# led_cube_final.net
KiCad netlist of a schematic drawn in EAGLE
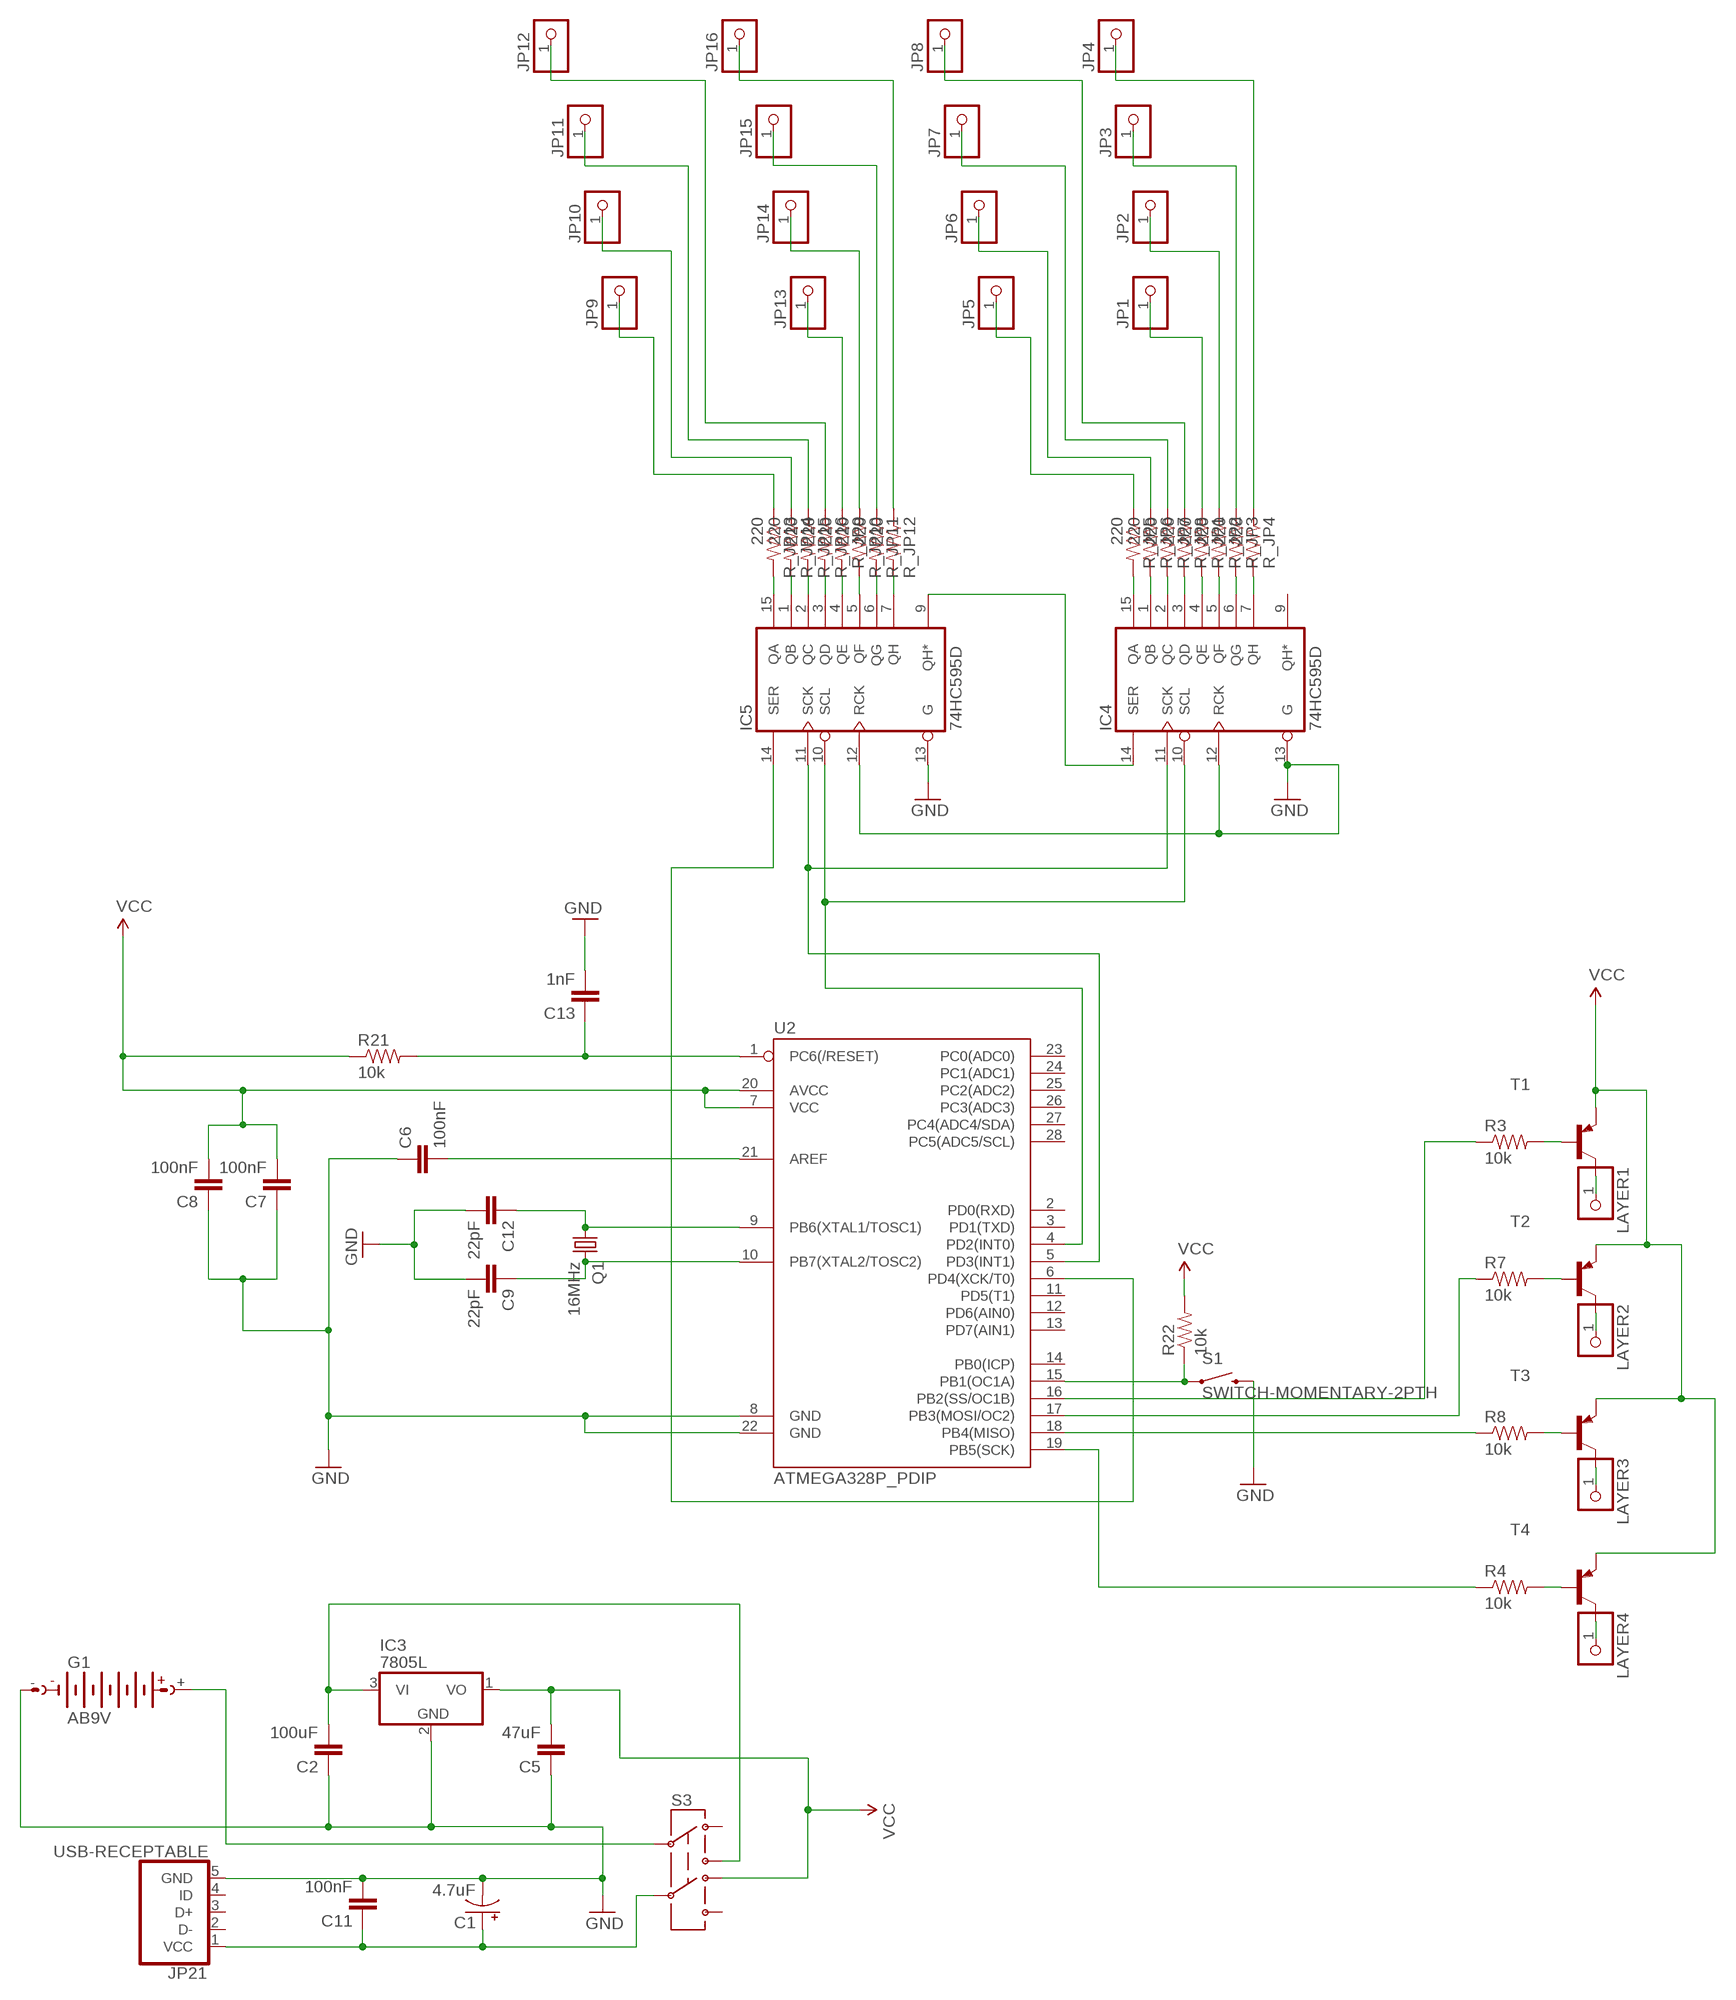
[diagram p0: schematic, sheet 1]

(export (version "E")
  (design (tool "Eeschema 10.0.6"))
  (components
    (comp (ref "C1")
      (value "4.7uF")
      (footprint "eagle-import:E2-5")
      (libsource (lib "eagle-import") (part "CPOL-USE2-5"))
    )
    (comp (ref "C2")
      (value "100uF")
      (footprint "eagle-import:0805")
      (libsource (lib "eagle-import") (part "CAP0805"))
    )
    (comp (ref "C5")
      (value "47uF")
      (footprint "eagle-import:0805")
      (libsource (lib "eagle-import") (part "CAP0805"))
    )
    (comp (ref "C6")
      (value "100nF")
      (footprint "eagle-import:0805")
      (libsource (lib "eagle-import") (part "CAP0805"))
    )
    (comp (ref "C7")
      (value "100nF")
      (footprint "eagle-import:0805")
      (libsource (lib "eagle-import") (part "CAP0805"))
    )
    (comp (ref "C8")
      (value "100nF")
      (footprint "eagle-import:0805")
      (libsource (lib "eagle-import") (part "CAP0805"))
    )
    (comp (ref "C9")
      (value "22pF")
      (footprint "eagle-import:0805")
      (libsource (lib "eagle-import") (part "CAP0805"))
    )
    (comp (ref "C11")
      (value "100nF")
      (footprint "eagle-import:0805")
      (libsource (lib "eagle-import") (part "CAP0805"))
    )
    (comp (ref "C12")
      (value "22pF")
      (footprint "eagle-import:0805")
      (libsource (lib "eagle-import") (part "CAP0805"))
    )
    (comp (ref "C13")
      (value "1nF")
      (footprint "eagle-import:0805")
      (libsource (lib "eagle-import") (part "CAP0805"))
    )
    (comp (ref "G1")
      (value "AB9V")
      (footprint "eagle-import:AB9V")
      (libsource (lib "eagle-import") (part "AB9V"))
    )
    (comp (ref "IC3")
      (value "7805L")
      (footprint "eagle-import:TO92")
      (libsource (lib "eagle-import") (part "78L05"))
    )
    (comp (ref "IC4")
      (value "74HC595D")
      (footprint "eagle-import:SO16")
      (libsource (lib "eagle-import") (part "74595DHC"))
    )
    (comp (ref "IC5")
      (value "74HC595D")
      (footprint "eagle-import:SO16")
      (libsource (lib "eagle-import") (part "74595DHC"))
    )
    (comp (ref "JP1")
      (value "PINHD-1X1")
      (footprint "eagle-import:1X01")
      (libsource (lib "eagle-import") (part "PINHD-1X1"))
    )
    (comp (ref "JP2")
      (value "PINHD-1X1")
      (footprint "eagle-import:1X01")
      (libsource (lib "eagle-import") (part "PINHD-1X1"))
    )
    (comp (ref "JP3")
      (value "PINHD-1X1")
      (footprint "eagle-import:1X01")
      (libsource (lib "eagle-import") (part "PINHD-1X1"))
    )
    (comp (ref "JP4")
      (value "PINHD-1X1")
      (footprint "eagle-import:1X01")
      (libsource (lib "eagle-import") (part "PINHD-1X1"))
    )
    (comp (ref "JP5")
      (value "PINHD-1X1")
      (footprint "eagle-import:1X01")
      (libsource (lib "eagle-import") (part "PINHD-1X1"))
    )
    (comp (ref "JP6")
      (value "PINHD-1X1")
      (footprint "eagle-import:1X01")
      (libsource (lib "eagle-import") (part "PINHD-1X1"))
    )
    (comp (ref "JP7")
      (value "PINHD-1X1")
      (footprint "eagle-import:1X01")
      (libsource (lib "eagle-import") (part "PINHD-1X1"))
    )
    (comp (ref "JP8")
      (value "PINHD-1X1")
      (footprint "eagle-import:1X01")
      (libsource (lib "eagle-import") (part "PINHD-1X1"))
    )
    (comp (ref "JP9")
      (value "PINHD-1X1")
      (footprint "eagle-import:1X01")
      (libsource (lib "eagle-import") (part "PINHD-1X1"))
    )
    (comp (ref "JP10")
      (value "PINHD-1X1")
      (footprint "eagle-import:1X01")
      (libsource (lib "eagle-import") (part "PINHD-1X1"))
    )
    (comp (ref "JP11")
      (value "PINHD-1X1")
      (footprint "eagle-import:1X01")
      (libsource (lib "eagle-import") (part "PINHD-1X1"))
    )
    (comp (ref "JP12")
      (value "PINHD-1X1")
      (footprint "eagle-import:1X01")
      (libsource (lib "eagle-import") (part "PINHD-1X1"))
    )
    (comp (ref "JP13")
      (value "PINHD-1X1")
      (footprint "eagle-import:1X01")
      (libsource (lib "eagle-import") (part "PINHD-1X1"))
    )
    (comp (ref "JP14")
      (value "PINHD-1X1")
      (footprint "eagle-import:1X01")
      (libsource (lib "eagle-import") (part "PINHD-1X1"))
    )
    (comp (ref "JP15")
      (value "PINHD-1X1")
      (footprint "eagle-import:1X01")
      (libsource (lib "eagle-import") (part "PINHD-1X1"))
    )
    (comp (ref "JP16")
      (value "PINHD-1X1")
      (footprint "eagle-import:1X01")
      (libsource (lib "eagle-import") (part "PINHD-1X1"))
    )
    (comp (ref "JP21")
      (value "USB-RECEPTABLE")
      (footprint "eagle-import:FCI-10103594-0001LF")
      (libsource (lib "eagle-import") (part "USB-RECEPTABLE"))
    )
    (comp (ref "LAYER1")
      (value "PINHD-1X1")
      (footprint "eagle-import:1X01")
      (libsource (lib "eagle-import") (part "PINHD-1X1"))
    )
    (comp (ref "LAYER2")
      (value "PINHD-1X1")
      (footprint "eagle-import:1X01")
      (libsource (lib "eagle-import") (part "PINHD-1X1"))
    )
    (comp (ref "LAYER3")
      (value "PINHD-1X1")
      (footprint "eagle-import:1X01")
      (libsource (lib "eagle-import") (part "PINHD-1X1"))
    )
    (comp (ref "LAYER4")
      (value "PINHD-1X1")
      (footprint "eagle-import:1X01")
      (libsource (lib "eagle-import") (part "PINHD-1X1"))
    )
    (comp (ref "Q1")
      (value "16MHz")
      (footprint "eagle-import:HC49_S")
      (libsource (lib "eagle-import") (part "CRYSTALHC49S"))
    )
    (comp (ref "R3")
      (value "10k")
      (footprint "eagle-import:0805")
      (libsource (lib "eagle-import") (part "RESISTOR0805-RES"))
    )
    (comp (ref "R4")
      (value "10k")
      (footprint "eagle-import:0805")
      (libsource (lib "eagle-import") (part "RESISTOR0805-RES"))
    )
    (comp (ref "R7")
      (value "10k")
      (footprint "eagle-import:0805")
      (libsource (lib "eagle-import") (part "RESISTOR0805-RES"))
    )
    (comp (ref "R8")
      (value "10k")
      (footprint "eagle-import:0805")
      (libsource (lib "eagle-import") (part "RESISTOR0805-RES"))
    )
    (comp (ref "R21")
      (value "10k")
      (footprint "eagle-import:0805")
      (libsource (lib "eagle-import") (part "RESISTOR0805-RES"))
    )
    (comp (ref "R22")
      (value "10k")
      (footprint "eagle-import:0805")
      (libsource (lib "eagle-import") (part "RESISTOR0805-RES"))
    )
    (comp (ref "R_JP1")
      (value "220")
      (footprint "eagle-import:0805")
      (libsource (lib "eagle-import") (part "RESISTOR0805-RES"))
    )
    (comp (ref "R_JP2")
      (value "220")
      (footprint "eagle-import:0805")
      (libsource (lib "eagle-import") (part "RESISTOR0805-RES"))
    )
    (comp (ref "R_JP3")
      (value "220")
      (footprint "eagle-import:0805")
      (libsource (lib "eagle-import") (part "RESISTOR0805-RES"))
    )
    (comp (ref "R_JP4")
      (value "220")
      (footprint "eagle-import:0805")
      (libsource (lib "eagle-import") (part "RESISTOR0805-RES"))
    )
    (comp (ref "R_JP5")
      (value "220")
      (footprint "eagle-import:0805")
      (libsource (lib "eagle-import") (part "RESISTOR0805-RES"))
    )
    (comp (ref "R_JP6")
      (value "220")
      (footprint "eagle-import:0805")
      (libsource (lib "eagle-import") (part "RESISTOR0805-RES"))
    )
    (comp (ref "R_JP7")
      (value "220")
      (footprint "eagle-import:0805")
      (libsource (lib "eagle-import") (part "RESISTOR0805-RES"))
    )
    (comp (ref "R_JP8")
      (value "220")
      (footprint "eagle-import:0805")
      (libsource (lib "eagle-import") (part "RESISTOR0805-RES"))
    )
    (comp (ref "R_JP9")
      (value "220")
      (footprint "eagle-import:0805")
      (libsource (lib "eagle-import") (part "RESISTOR0805-RES"))
    )
    (comp (ref "R_JP10")
      (value "220")
      (footprint "eagle-import:0805")
      (libsource (lib "eagle-import") (part "RESISTOR0805-RES"))
    )
    (comp (ref "R_JP11")
      (value "220")
      (footprint "eagle-import:0805")
      (libsource (lib "eagle-import") (part "RESISTOR0805-RES"))
    )
    (comp (ref "R_JP12")
      (value "220")
      (footprint "eagle-import:0805")
      (libsource (lib "eagle-import") (part "RESISTOR0805-RES"))
    )
    (comp (ref "R_JP13")
      (value "220")
      (footprint "eagle-import:0805")
      (libsource (lib "eagle-import") (part "RESISTOR0805-RES"))
    )
    (comp (ref "R_JP14")
      (value "220")
      (footprint "eagle-import:0805")
      (libsource (lib "eagle-import") (part "RESISTOR0805-RES"))
    )
    (comp (ref "R_JP15")
      (value "220")
      (footprint "eagle-import:0805")
      (libsource (lib "eagle-import") (part "RESISTOR0805-RES"))
    )
    (comp (ref "R_JP16")
      (value "220")
      (footprint "eagle-import:0805")
      (libsource (lib "eagle-import") (part "RESISTOR0805-RES"))
    )
    (comp (ref "S1")
      (value "SWITCH-MOMENTARY-2PTH")
      (footprint "eagle-import:TACTILE-PTH")
      (libsource (lib "eagle-import") (part "SWITCH-MOMENTARY-2PTH"))
    )
    (comp (ref "S3")
      (value "SWITCH-DPDTOS")
      (footprint "eagle-import:OS")
      (libsource (lib "eagle-import") (part "SWITCH-DPDTOS"))
    )
    (comp (ref "T1")
      (value "BC327-16-PNP-TO92-EBC")
      (footprint "eagle-import:TO92-EBC")
      (libsource (lib "eagle-import") (part "-PNP-TO92-EBCBC327-16"))
    )
    (comp (ref "T2")
      (value "BC327-16-PNP-TO92-EBC")
      (footprint "eagle-import:TO92-EBC")
      (libsource (lib "eagle-import") (part "-PNP-TO92-EBCBC327-16"))
    )
    (comp (ref "T3")
      (value "BC327-16-PNP-TO92-EBC")
      (footprint "eagle-import:TO92-EBC")
      (libsource (lib "eagle-import") (part "-PNP-TO92-EBCBC327-16"))
    )
    (comp (ref "T4")
      (value "BC327-16-PNP-TO92-EBC")
      (footprint "eagle-import:TO92-EBC")
      (libsource (lib "eagle-import") (part "-PNP-TO92-EBCBC327-16"))
    )
    (comp (ref "U2")
      (value "ATMEGA328P_PDIP")
      (footprint "eagle-import:DIL28-3")
      (libsource (lib "eagle-import") (part "ATMEGA328P_PDIP"))
    )
  )
  (nets
    (net (code "1") (name "GND") (class "Default")
      (node (ref "C1") (pin "-") (pinfunction "-_-") (pintype "passive"))
      (node (ref "C11") (pin "2") (pinfunction "2_2") (pintype "passive"))
      (node (ref "C12") (pin "2") (pinfunction "2_2") (pintype "passive"))
      (node (ref "C13") (pin "2") (pinfunction "2_2") (pintype "passive"))
      (node (ref "C2") (pin "1") (pinfunction "1_1") (pintype "passive"))
      (node (ref "C5") (pin "1") (pinfunction "1_1") (pintype "passive"))
      (node (ref "C6") (pin "1") (pinfunction "1_1") (pintype "passive"))
      (node (ref "C7") (pin "1") (pinfunction "1_1") (pintype "passive"))
      (node (ref "C8") (pin "1") (pinfunction "1_1") (pintype "passive"))
      (node (ref "C9") (pin "2") (pinfunction "2_2") (pintype "passive"))
      (node (ref "G1") (pin "-") (pinfunction "-_-") (pintype "passive"))
      (node (ref "IC3") (pin "2") (pinfunction "GND_2") (pintype "passive"))
      (node (ref "IC4") (pin "12") (pinfunction "RCK_12") (pintype "input"))
      (node (ref "IC4") (pin "13") (pinfunction "G_13") (pintype "input"))
      (node (ref "IC5") (pin "12") (pinfunction "RCK_12") (pintype "input"))
      (node (ref "IC5") (pin "13") (pinfunction "G_13") (pintype "input"))
      (node (ref "JP21") (pin "5") (pinfunction "GND_5") (pintype "bidirectional"))
      (node (ref "S1") (pin "3") (pinfunction "2_3") (pintype "passive"))
      (node (ref "U2") (pin "22") (pinfunction "GND_22") (pintype "bidirectional"))
      (node (ref "U2") (pin "8") (pinfunction "GND_8") (pintype "bidirectional"))
    )
    (net (code "2") (name "Net-(G1-Pad+)") (class "Default")
      (node (ref "G1") (pin "+") (pinfunction "+_+") (pintype "passive"))
      (node (ref "S3") (pin "2") (pinfunction "2_2") (pintype "bidirectional"))
    )
    (net (code "3") (name "Net-(IC3-VI)") (class "Default")
      (node (ref "C2") (pin "2") (pinfunction "2_2") (pintype "passive"))
      (node (ref "IC3") (pin "3") (pinfunction "VI_3") (pintype "input"))
      (node (ref "S3") (pin "3") (pinfunction "3_3") (pintype "bidirectional"))
    )
    (net (code "4") (name "Net-(IC4A-QA)") (class "Default")
      (node (ref "IC4") (pin "15") (pinfunction "QA_15") (pintype "tri_state"))
      (node (ref "R_JP5") (pin "2") (pinfunction "2_2") (pintype "passive"))
    )
    (net (code "5") (name "Net-(IC4A-QB)") (class "Default")
      (node (ref "IC4") (pin "1") (pinfunction "QB_1") (pintype "tri_state"))
      (node (ref "R_JP6") (pin "2") (pinfunction "2_2") (pintype "passive"))
    )
    (net (code "6") (name "Net-(IC4A-QC)") (class "Default")
      (node (ref "IC4") (pin "2") (pinfunction "QC_2") (pintype "tri_state"))
      (node (ref "R_JP7") (pin "2") (pinfunction "2_2") (pintype "passive"))
    )
    (net (code "7") (name "Net-(IC4A-QD)") (class "Default")
      (node (ref "IC4") (pin "3") (pinfunction "QD_3") (pintype "tri_state"))
      (node (ref "R_JP8") (pin "2") (pinfunction "2_2") (pintype "passive"))
    )
    (net (code "8") (name "Net-(IC4A-QE)") (class "Default")
      (node (ref "IC4") (pin "4") (pinfunction "QE_4") (pintype "tri_state"))
      (node (ref "R_JP1") (pin "2") (pinfunction "2_2") (pintype "passive"))
    )
    (net (code "9") (name "Net-(IC4A-QF)") (class "Default")
      (node (ref "IC4") (pin "5") (pinfunction "QF_5") (pintype "tri_state"))
      (node (ref "R_JP2") (pin "2") (pinfunction "2_2") (pintype "passive"))
    )
    (net (code "10") (name "Net-(IC4A-QG)") (class "Default")
      (node (ref "IC4") (pin "6") (pinfunction "QG_6") (pintype "tri_state"))
      (node (ref "R_JP3") (pin "2") (pinfunction "2_2") (pintype "passive"))
    )
    (net (code "11") (name "Net-(IC4A-QH)") (class "Default")
      (node (ref "IC4") (pin "7") (pinfunction "QH_7") (pintype "tri_state"))
      (node (ref "R_JP4") (pin "2") (pinfunction "2_2") (pintype "passive"))
    )
    (net (code "12") (name "Net-(IC4A-SCK)") (class "Default")
      (node (ref "IC4") (pin "11") (pinfunction "SCK_11") (pintype "input"))
      (node (ref "IC5") (pin "11") (pinfunction "SCK_11") (pintype "input"))
      (node (ref "U2") (pin "5") (pinfunction "PD3(INT1)_5") (pintype "bidirectional"))
    )
    (net (code "13") (name "Net-(IC4A-SCL)") (class "Default")
      (node (ref "IC4") (pin "10") (pinfunction "SCL_10") (pintype "input"))
      (node (ref "IC5") (pin "10") (pinfunction "SCL_10") (pintype "input"))
      (node (ref "U2") (pin "4") (pinfunction "PD2(INT0)_4") (pintype "bidirectional"))
    )
    (net (code "14") (name "Net-(IC4A-SER)") (class "Default")
      (node (ref "IC4") (pin "14") (pinfunction "SER_14") (pintype "input"))
      (node (ref "IC5") (pin "9") (pinfunction "QH*_9") (pintype "tri_state"))
    )
    (net (code "15") (name "Net-(IC5A-QA)") (class "Default")
      (node (ref "IC5") (pin "15") (pinfunction "QA_15") (pintype "tri_state"))
      (node (ref "R_JP13") (pin "2") (pinfunction "2_2") (pintype "passive"))
    )
    (net (code "16") (name "Net-(IC5A-QB)") (class "Default")
      (node (ref "IC5") (pin "1") (pinfunction "QB_1") (pintype "tri_state"))
      (node (ref "R_JP14") (pin "2") (pinfunction "2_2") (pintype "passive"))
    )
    (net (code "17") (name "Net-(IC5A-QC)") (class "Default")
      (node (ref "IC5") (pin "2") (pinfunction "QC_2") (pintype "tri_state"))
      (node (ref "R_JP15") (pin "2") (pinfunction "2_2") (pintype "passive"))
    )
    (net (code "18") (name "Net-(IC5A-QD)") (class "Default")
      (node (ref "IC5") (pin "3") (pinfunction "QD_3") (pintype "tri_state"))
      (node (ref "R_JP16") (pin "2") (pinfunction "2_2") (pintype "passive"))
    )
    (net (code "19") (name "Net-(IC5A-QE)") (class "Default")
      (node (ref "IC5") (pin "4") (pinfunction "QE_4") (pintype "tri_state"))
      (node (ref "R_JP9") (pin "2") (pinfunction "2_2") (pintype "passive"))
    )
    (net (code "20") (name "Net-(IC5A-QF)") (class "Default")
      (node (ref "IC5") (pin "5") (pinfunction "QF_5") (pintype "tri_state"))
      (node (ref "R_JP10") (pin "2") (pinfunction "2_2") (pintype "passive"))
    )
    (net (code "21") (name "Net-(IC5A-QG)") (class "Default")
      (node (ref "IC5") (pin "6") (pinfunction "QG_6") (pintype "tri_state"))
      (node (ref "R_JP11") (pin "2") (pinfunction "2_2") (pintype "passive"))
    )
    (net (code "22") (name "Net-(IC5A-QH)") (class "Default")
      (node (ref "IC5") (pin "7") (pinfunction "QH_7") (pintype "tri_state"))
      (node (ref "R_JP12") (pin "2") (pinfunction "2_2") (pintype "passive"))
    )
    (net (code "23") (name "Net-(IC5A-SER)") (class "Default")
      (node (ref "IC5") (pin "14") (pinfunction "SER_14") (pintype "input"))
      (node (ref "U2") (pin "6") (pinfunction "PD4(XCK/T0)_6") (pintype "bidirectional"))
    )
    (net (code "24") (name "Net-(JP1-Pad1)") (class "Default")
      (node (ref "JP1") (pin "1") (pinfunction "1_1") (pintype "passive"))
      (node (ref "R_JP1") (pin "1") (pinfunction "1_1") (pintype "passive"))
    )
    (net (code "25") (name "Net-(JP2-Pad1)") (class "Default")
      (node (ref "JP2") (pin "1") (pinfunction "1_1") (pintype "passive"))
      (node (ref "R_JP2") (pin "1") (pinfunction "1_1") (pintype "passive"))
    )
    (net (code "26") (name "Net-(JP3-Pad1)") (class "Default")
      (node (ref "JP3") (pin "1") (pinfunction "1_1") (pintype "passive"))
      (node (ref "R_JP3") (pin "1") (pinfunction "1_1") (pintype "passive"))
    )
    (net (code "27") (name "Net-(JP4-Pad1)") (class "Default")
      (node (ref "JP4") (pin "1") (pinfunction "1_1") (pintype "passive"))
      (node (ref "R_JP4") (pin "1") (pinfunction "1_1") (pintype "passive"))
    )
    (net (code "28") (name "Net-(JP5-Pad1)") (class "Default")
      (node (ref "JP5") (pin "1") (pinfunction "1_1") (pintype "passive"))
      (node (ref "R_JP5") (pin "1") (pinfunction "1_1") (pintype "passive"))
    )
    (net (code "29") (name "Net-(JP6-Pad1)") (class "Default")
      (node (ref "JP6") (pin "1") (pinfunction "1_1") (pintype "passive"))
      (node (ref "R_JP6") (pin "1") (pinfunction "1_1") (pintype "passive"))
    )
    (net (code "30") (name "Net-(JP7-Pad1)") (class "Default")
      (node (ref "JP7") (pin "1") (pinfunction "1_1") (pintype "passive"))
      (node (ref "R_JP7") (pin "1") (pinfunction "1_1") (pintype "passive"))
    )
    (net (code "31") (name "Net-(JP8-Pad1)") (class "Default")
      (node (ref "JP8") (pin "1") (pinfunction "1_1") (pintype "passive"))
      (node (ref "R_JP8") (pin "1") (pinfunction "1_1") (pintype "passive"))
    )
    (net (code "32") (name "Net-(JP9-Pad1)") (class "Default")
      (node (ref "JP9") (pin "1") (pinfunction "1_1") (pintype "passive"))
      (node (ref "R_JP13") (pin "1") (pinfunction "1_1") (pintype "passive"))
    )
    (net (code "33") (name "Net-(JP10-Pad1)") (class "Default")
      (node (ref "JP10") (pin "1") (pinfunction "1_1") (pintype "passive"))
      (node (ref "R_JP14") (pin "1") (pinfunction "1_1") (pintype "passive"))
    )
    (net (code "34") (name "Net-(JP11-Pad1)") (class "Default")
      (node (ref "JP11") (pin "1") (pinfunction "1_1") (pintype "passive"))
      (node (ref "R_JP15") (pin "1") (pinfunction "1_1") (pintype "passive"))
    )
    (net (code "35") (name "Net-(JP12-Pad1)") (class "Default")
      (node (ref "JP12") (pin "1") (pinfunction "1_1") (pintype "passive"))
      (node (ref "R_JP16") (pin "1") (pinfunction "1_1") (pintype "passive"))
    )
    (net (code "36") (name "Net-(JP13-Pad1)") (class "Default")
      (node (ref "JP13") (pin "1") (pinfunction "1_1") (pintype "passive"))
      (node (ref "R_JP9") (pin "1") (pinfunction "1_1") (pintype "passive"))
    )
    (net (code "37") (name "Net-(JP14-Pad1)") (class "Default")
      (node (ref "JP14") (pin "1") (pinfunction "1_1") (pintype "passive"))
      (node (ref "R_JP10") (pin "1") (pinfunction "1_1") (pintype "passive"))
    )
    (net (code "38") (name "Net-(JP15-Pad1)") (class "Default")
      (node (ref "JP15") (pin "1") (pinfunction "1_1") (pintype "passive"))
      (node (ref "R_JP11") (pin "1") (pinfunction "1_1") (pintype "passive"))
    )
    (net (code "39") (name "Net-(JP16-Pad1)") (class "Default")
      (node (ref "JP16") (pin "1") (pinfunction "1_1") (pintype "passive"))
      (node (ref "R_JP12") (pin "1") (pinfunction "1_1") (pintype "passive"))
    )
    (net (code "40") (name "Net-(JP21-VCC)") (class "Default")
      (node (ref "C1") (pin "+") (pinfunction "+_+") (pintype "passive"))
      (node (ref "C11") (pin "1") (pinfunction "1_1") (pintype "passive"))
      (node (ref "JP21") (pin "1") (pinfunction "VCC_1") (pintype "bidirectional"))
      (node (ref "S3") (pin "5") (pinfunction "5_5") (pintype "bidirectional"))
    )
    (net (code "41") (name "Net-(LAYER1-Pad1)") (class "Default")
      (node (ref "LAYER1") (pin "1") (pinfunction "1_1") (pintype "passive"))
      (node (ref "T1") (pin "C") (pinfunction "C_C") (pintype "passive"))
    )
    (net (code "42") (name "Net-(LAYER2-Pad1)") (class "Default")
      (node (ref "LAYER2") (pin "1") (pinfunction "1_1") (pintype "passive"))
      (node (ref "T2") (pin "C") (pinfunction "C_C") (pintype "passive"))
    )
    (net (code "43") (name "Net-(LAYER3-Pad1)") (class "Default")
      (node (ref "LAYER3") (pin "1") (pinfunction "1_1") (pintype "passive"))
      (node (ref "T3") (pin "C") (pinfunction "C_C") (pintype "passive"))
    )
    (net (code "44") (name "Net-(LAYER4-Pad1)") (class "Default")
      (node (ref "LAYER4") (pin "1") (pinfunction "1_1") (pintype "passive"))
      (node (ref "T4") (pin "C") (pinfunction "C_C") (pintype "passive"))
    )
    (net (code "45") (name "Net-(R3-Pad2)") (class "Default")
      (node (ref "R3") (pin "2") (pinfunction "2_2") (pintype "passive"))
      (node (ref "T1") (pin "B") (pinfunction "B_B") (pintype "passive"))
    )
    (net (code "46") (name "Net-(R4-Pad2)") (class "Default")
      (node (ref "R4") (pin "2") (pinfunction "2_2") (pintype "passive"))
      (node (ref "T4") (pin "B") (pinfunction "B_B") (pintype "passive"))
    )
    (net (code "47") (name "Net-(R7-Pad2)") (class "Default")
      (node (ref "R7") (pin "2") (pinfunction "2_2") (pintype "passive"))
      (node (ref "T2") (pin "B") (pinfunction "B_B") (pintype "passive"))
    )
    (net (code "48") (name "Net-(R8-Pad2)") (class "Default")
      (node (ref "R8") (pin "2") (pinfunction "2_2") (pintype "passive"))
      (node (ref "T3") (pin "B") (pinfunction "B_B") (pintype "passive"))
    )
    (net (code "49") (name "Net-(U2-AREF)") (class "Default")
      (node (ref "C6") (pin "2") (pinfunction "2_2") (pintype "passive"))
      (node (ref "U2") (pin "21") (pinfunction "AREF_21") (pintype "bidirectional"))
    )
    (net (code "50") (name "Net-(U2-PB1(OC1A))") (class "Default")
      (node (ref "R22") (pin "1") (pinfunction "1_1") (pintype "passive"))
      (node (ref "S1") (pin "1") (pinfunction "1_1") (pintype "passive"))
      (node (ref "U2") (pin "15") (pinfunction "PB1(OC1A)_15") (pintype "bidirectional"))
    )
    (net (code "51") (name "Net-(U2-PB2(SS{slash}OC1B))") (class "Default")
      (node (ref "R3") (pin "1") (pinfunction "1_1") (pintype "passive"))
      (node (ref "U2") (pin "16") (pinfunction "PB2(SS/OC1B)_16") (pintype "bidirectional"))
    )
    (net (code "52") (name "Net-(U2-PB3(MOSI{slash}OC2))") (class "Default")
      (node (ref "R7") (pin "1") (pinfunction "1_1") (pintype "passive"))
      (node (ref "U2") (pin "17") (pinfunction "PB3(MOSI/OC2)_17") (pintype "bidirectional"))
    )
    (net (code "53") (name "Net-(U2-PB4(MISO))") (class "Default")
      (node (ref "R8") (pin "1") (pinfunction "1_1") (pintype "passive"))
      (node (ref "U2") (pin "18") (pinfunction "PB4(MISO)_18") (pintype "bidirectional"))
    )
    (net (code "54") (name "Net-(U2-PB5(SCK))") (class "Default")
      (node (ref "R4") (pin "1") (pinfunction "1_1") (pintype "passive"))
      (node (ref "U2") (pin "19") (pinfunction "PB5(SCK)_19") (pintype "bidirectional"))
    )
    (net (code "55") (name "Net-(U2-PB6(XTAL1{slash}TOSC1))") (class "Default")
      (node (ref "C12") (pin "1") (pinfunction "1_1") (pintype "passive"))
      (node (ref "Q1") (pin "1") (pinfunction "1_1") (pintype "passive"))
      (node (ref "U2") (pin "9") (pinfunction "PB6(XTAL1/TOSC1)_9") (pintype "bidirectional"))
    )
    (net (code "56") (name "Net-(U2-PB7(XTAL2{slash}TOSC2))") (class "Default")
      (node (ref "C9") (pin "1") (pinfunction "1_1") (pintype "passive"))
      (node (ref "Q1") (pin "2") (pinfunction "2_2") (pintype "passive"))
      (node (ref "U2") (pin "10") (pinfunction "PB7(XTAL2/TOSC2)_10") (pintype "bidirectional"))
    )
    (net (code "57") (name "Net-(U2-PC6({slash}RESET))") (class "Default")
      (node (ref "C13") (pin "1") (pinfunction "1_1") (pintype "passive"))
      (node (ref "R21") (pin "2") (pinfunction "2_2") (pintype "passive"))
      (node (ref "U2") (pin "1") (pinfunction "PC6(/RESET)_1") (pintype "bidirectional"))
    )
    (net (code "58") (name "VCC") (class "Default")
      (node (ref "C5") (pin "2") (pinfunction "2_2") (pintype "passive"))
      (node (ref "C7") (pin "2") (pinfunction "2_2") (pintype "passive"))
      (node (ref "C8") (pin "2") (pinfunction "2_2") (pintype "passive"))
      (node (ref "IC3") (pin "1") (pinfunction "VO_1") (pintype "passive"))
      (node (ref "R21") (pin "1") (pinfunction "1_1") (pintype "passive"))
      (node (ref "R22") (pin "2") (pinfunction "2_2") (pintype "passive"))
      (node (ref "S3") (pin "4") (pinfunction "4_4") (pintype "bidirectional"))
      (node (ref "T1") (pin "E") (pinfunction "E_E") (pintype "passive"))
      (node (ref "T2") (pin "E") (pinfunction "E_E") (pintype "passive"))
      (node (ref "T3") (pin "E") (pinfunction "E_E") (pintype "passive"))
      (node (ref "T4") (pin "E") (pinfunction "E_E") (pintype "passive"))
      (node (ref "U2") (pin "20") (pinfunction "AVCC_20") (pintype "bidirectional"))
      (node (ref "U2") (pin "7") (pinfunction "VCC_7") (pintype "bidirectional"))
    )
    (net (code "59") (name "unconnected-(IC4A-QH*-Pad9)") (class "Default")
      (node (ref "IC4") (pin "9") (pinfunction "QH*_9") (pintype "tri_state"))
    )
    (net (code "60") (name "unconnected-(JP21-D+-Pad3)") (class "Default")
      (node (ref "JP21") (pin "3") (pinfunction "D+_3") (pintype "bidirectional"))
    )
    (net (code "61") (name "unconnected-(JP21-D--Pad2)") (class "Default")
      (node (ref "JP21") (pin "2") (pinfunction "D-_2") (pintype "bidirectional"))
    )
    (net (code "62") (name "unconnected-(JP21-ID-Pad4)") (class "Default")
      (node (ref "JP21") (pin "4") (pinfunction "ID_4") (pintype "bidirectional"))
    )
    (net (code "63") (name "unconnected-(S3-Pad1)") (class "Default")
      (node (ref "S3") (pin "1") (pinfunction "1_1") (pintype "bidirectional"))
    )
    (net (code "64") (name "unconnected-(S3-Pad6)") (class "Default")
      (node (ref "S3") (pin "6") (pinfunction "6_6") (pintype "bidirectional"))
    )
    (net (code "65") (name "unconnected-(U2-PB0(ICP)-Pad14)") (class "Default")
      (node (ref "U2") (pin "14") (pinfunction "PB0(ICP)_14") (pintype "bidirectional"))
    )
    (net (code "66") (name "unconnected-(U2-PC0(ADC0)-Pad23)") (class "Default")
      (node (ref "U2") (pin "23") (pinfunction "PC0(ADC0)_23") (pintype "bidirectional"))
    )
    (net (code "67") (name "unconnected-(U2-PC1(ADC1)-Pad24)") (class "Default")
      (node (ref "U2") (pin "24") (pinfunction "PC1(ADC1)_24") (pintype "bidirectional"))
    )
    (net (code "68") (name "unconnected-(U2-PC2(ADC2)-Pad25)") (class "Default")
      (node (ref "U2") (pin "25") (pinfunction "PC2(ADC2)_25") (pintype "bidirectional"))
    )
    (net (code "69") (name "unconnected-(U2-PC3(ADC3)-Pad26)") (class "Default")
      (node (ref "U2") (pin "26") (pinfunction "PC3(ADC3)_26") (pintype "bidirectional"))
    )
    (net (code "70") (name "unconnected-(U2-PC4(ADC4{slash}SDA)-Pad27)") (class "Default")
      (node (ref "U2") (pin "27") (pinfunction "PC4(ADC4/SDA)_27") (pintype "bidirectional"))
    )
    (net (code "71") (name "unconnected-(U2-PC5(ADC5{slash}SCL)-Pad28)") (class "Default")
      (node (ref "U2") (pin "28") (pinfunction "PC5(ADC5/SCL)_28") (pintype "bidirectional"))
    )
    (net (code "72") (name "unconnected-(U2-PD0(RXD)-Pad2)") (class "Default")
      (node (ref "U2") (pin "2") (pinfunction "PD0(RXD)_2") (pintype "bidirectional"))
    )
    (net (code "73") (name "unconnected-(U2-PD1(TXD)-Pad3)") (class "Default")
      (node (ref "U2") (pin "3") (pinfunction "PD1(TXD)_3") (pintype "bidirectional"))
    )
    (net (code "74") (name "unconnected-(U2-PD5(T1)-Pad11)") (class "Default")
      (node (ref "U2") (pin "11") (pinfunction "PD5(T1)_11") (pintype "bidirectional"))
    )
    (net (code "75") (name "unconnected-(U2-PD6(AIN0)-Pad12)") (class "Default")
      (node (ref "U2") (pin "12") (pinfunction "PD6(AIN0)_12") (pintype "bidirectional"))
    )
    (net (code "76") (name "unconnected-(U2-PD7(AIN1)-Pad13)") (class "Default")
      (node (ref "U2") (pin "13") (pinfunction "PD7(AIN1)_13") (pintype "bidirectional"))
    )
  )
)
